# MCU.net
KiCad netlist of a schematic drawn in Altium Designer
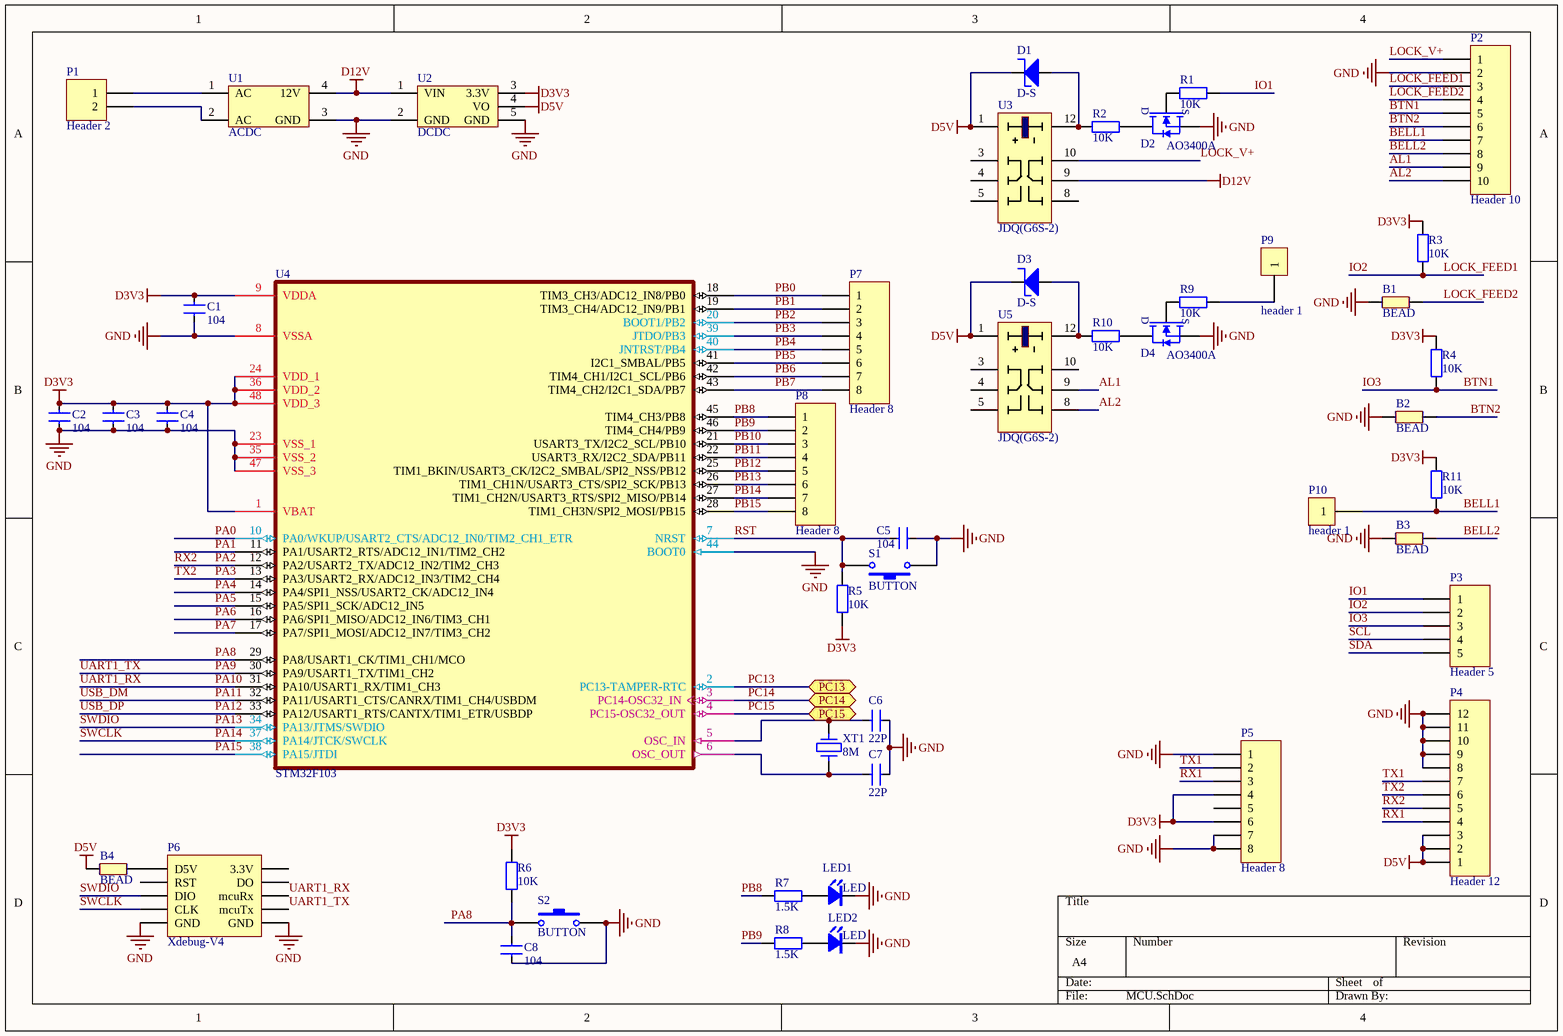
[diagram p0: MCU.SchDoc]

(export (version "E")
  (design (tool "Eeschema 10.0.6"))
  (components
    (comp (ref "B1")
      (value "BEAD")
      (footprint "0603L")
      (description "磁珠")
      (libsource (lib "lib_AD") (part "BEAD"))
    )
    (comp (ref "B2")
      (value "BEAD")
      (footprint "0603L")
      (description "磁珠")
      (libsource (lib "lib_AD") (part "BEAD"))
    )
    (comp (ref "B3")
      (value "BEAD")
      (footprint "0603L")
      (description "磁珠")
      (libsource (lib "lib_AD") (part "BEAD"))
    )
    (comp (ref "B4")
      (value "BEAD")
      (footprint "0603L")
      (description "磁珠")
      (libsource (lib "lib_AD") (part "BEAD"))
    )
    (comp (ref "C1")
      (value "104")
      (footprint "0603C")
      (description "普通小电容")
      (libsource (lib "lib_GMDZ") (part "CAP"))
    )
    (comp (ref "C2")
      (value "104")
      (footprint "0603C")
      (description "普通小电容")
      (libsource (lib "lib_GMDZ") (part "CAP"))
    )
    (comp (ref "C3")
      (value "104")
      (footprint "0603C")
      (description "普通小电容")
      (libsource (lib "lib_GMDZ") (part "CAP"))
    )
    (comp (ref "C4")
      (value "104")
      (footprint "0603C")
      (description "普通小电容")
      (libsource (lib "lib_GMDZ") (part "CAP"))
    )
    (comp (ref "C5")
      (value "104")
      (footprint "0603C")
      (description "普通小电容")
      (libsource (lib "lib_AD") (part "CAP"))
    )
    (comp (ref "C6")
      (value "22P")
      (footprint "0603C")
      (description "普通小电容")
      (libsource (lib "lib_AD") (part "CAP"))
    )
    (comp (ref "C7")
      (value "22P")
      (footprint "0603C")
      (description "普通小电容")
      (libsource (lib "lib_AD") (part "CAP"))
    )
    (comp (ref "C8")
      (value "104")
      (footprint "0603C")
      (description "普通小电容")
      (libsource (lib "lib_AD") (part "CAP"))
    )
    (comp (ref "D1")
      (value "D-S")
      (footprint "DO-214AC(SMA)")
      (description "肖特基二极管")
      (libsource (lib "lib_AD") (part "D-S"))
    )
    (comp (ref "D2")
      (value "AO3400A")
      (footprint "SOT23A")
      (description "NMOS")
      (libsource (lib "lib_AD") (part "MOS-N"))
    )
    (comp (ref "D3")
      (value "D-S")
      (footprint "DO-214AC(SMA)")
      (description "肖特基二极管")
      (libsource (lib "lib_AD") (part "D-S"))
    )
    (comp (ref "D4")
      (value "AO3400A")
      (footprint "SOT23A")
      (description "NMOS")
      (libsource (lib "lib_AD") (part "MOS-N"))
    )
    (comp (ref "LED1") (value "LED") (footprint "0805D") (libsource (lib "lib_AD") (part "LED")))
    (comp (ref "LED2") (value "LED") (footprint "0805D") (libsource (lib "lib_AD") (part "LED")))
    (comp (ref "P1")
      (value "Header 2")
      (footprint "KF128-5.08-2")
      (description "Header, 2-Pin")
      (fields (field (name "PUBLISHER") "Altium Limited"))
      (libsource (lib "Header") (part "Header 2"))
    )
    (comp (ref "P2")
      (value "Header 10")
      (footprint "KF128-5.08-10")
      (description "Header, 10-Pin")
      (fields (field (name "PUBLISHER") "Altium Limited"))
      (libsource (lib "lib_AD") (part "Header 10"))
    )
    (comp (ref "P3")
      (value "Header 5")
      (footprint "HDR1X5")
      (description "Header, 5-Pin")
      (fields (field (name "PUBLISHER") "Altium Limited"))
      (libsource (lib "lib_AD") (part "Header 5"))
    )
    (comp (ref "P4")
      (value "Header 12")
      (footprint "FFC/SM1.0-2H10")
      (description "Header, 12-Pin")
      (fields (field (name "PUBLISHER") "Altium Limited"))
      (libsource (lib "lib_AD") (part "Header 12"))
    )
    (comp (ref "P5")
      (value "Header 8")
      (footprint "1.25T-6P")
      (description "Header, 8-Pin")
      (fields (field (name "PUBLISHER") "Altium Limited"))
      (libsource (lib "lib_AD") (part "Header 8"))
    )
    (comp (ref "P6")
      (value "Xdebug-V4")
      (footprint "DC2.54-10")
      (description "单片机端")
      (libsource (lib "lib_AD") (part "Xdebug-V4"))
    )
    (comp (ref "P7")
      (value "Header 8")
      (footprint "HDR1X8")
      (description "Header, 8-Pin")
      (fields (field (name "PUBLISHER") "Altium Limited"))
      (libsource (lib "lib_AD") (part "Header 8"))
    )
    (comp (ref "P8")
      (value "Header 8")
      (footprint "HDR1X8")
      (description "Header, 8-Pin")
      (fields (field (name "PUBLISHER") "Altium Limited"))
      (libsource (lib "lib_AD") (part "Header 8"))
    )
    (comp (ref "P9") (value "header 1") (footprint "HDR1") (libsource (lib "") (part "header 1_1")))
    (comp (ref "P10") (value "header 1") (footprint "HDR1") (libsource (lib "lib_AD") (part "header 1")))
    (comp (ref "R1")
      (value "10K")
      (footprint "0603R")
      (description "普通电阻")
      (libsource (lib "lib_AD") (part "RES"))
    )
    (comp (ref "R2")
      (value "10K")
      (footprint "0603R")
      (description "普通电阻")
      (libsource (lib "lib_AD") (part "RES"))
    )
    (comp (ref "R3")
      (value "10K")
      (footprint "0603R")
      (description "普通电阻")
      (libsource (lib "") (part "RES_2"))
    )
    (comp (ref "R4")
      (value "10K")
      (footprint "0603R")
      (description "普通电阻")
      (libsource (lib "") (part "RES_2"))
    )
    (comp (ref "R5")
      (value "10K")
      (footprint "0603R")
      (description "普通电阻")
      (libsource (lib "") (part "RES_2"))
    )
    (comp (ref "R6")
      (value "10K")
      (footprint "0603R")
      (description "普通电阻")
      (libsource (lib "") (part "RES_3"))
    )
    (comp (ref "R7")
      (value "1.5K")
      (footprint "0603R")
      (description "普通电阻")
      (libsource (lib "") (part "RES_1"))
    )
    (comp (ref "R8")
      (value "1.5K")
      (footprint "0603R")
      (description "普通电阻")
      (libsource (lib "") (part "RES_1"))
    )
    (comp (ref "R9")
      (value "10K")
      (footprint "0603R")
      (description "普通电阻")
      (libsource (lib "lib_AD") (part "RES"))
    )
    (comp (ref "R10")
      (value "10K")
      (footprint "0603R")
      (description "普通电阻")
      (libsource (lib "lib_AD") (part "RES"))
    )
    (comp (ref "R11")
      (value "10K")
      (footprint "0603R")
      (description "普通电阻")
      (libsource (lib "") (part "RES_2"))
    )
    (comp (ref "S1") (value "BUTTON") (footprint "SW-3X4X2") (libsource (lib "lib_AD") (part "BUTTON")))
    (comp (ref "S2") (value "BUTTON") (footprint "SW-3X4X2") (libsource (lib "lib_AD") (part "BUTTON")))
    (comp (ref "U1") (value "ACDC") (footprint "ACDC") (libsource (lib "Misc") (part "ACDC12")))
    (comp (ref "U2") (value "DCDC") (footprint "DCDC") (libsource (lib "lib_AD") (part "DCDC")))
    (comp (ref "U3")
      (value "JDQ(G6S-2)")
      (footprint "JDQ-G6S-2")
      (description "继电器（G6S-2 5VDC）")
      (libsource (lib "lib_AD") (part "JDQ(G6S-2)"))
    )
    (comp (ref "U4") (value "STM32F103") (footprint "LQFP48") (libsource (lib "lib_GMDZ") (part "STM32F103")))
    (comp (ref "U5")
      (value "JDQ(G6S-2)")
      (footprint "JDQ-G6S-2")
      (description "继电器（G6S-2 5VDC）")
      (libsource (lib "lib_AD") (part "JDQ(G6S-2)"))
    )
    (comp (ref "XT1")
      (value "8M")
      (footprint "5032")
      (description "晶振")
      (libsource (lib "lib_GMDZ") (part "XT"))
    )
  )
  (nets
    (net (code "1") (name "/AL1") (class "Default")
      (node (ref "P2") (pin "9") (pinfunction "9_9") (pintype "passive"))
      (node (ref "U5") (pin "9") (pinfunction "9_9") (pintype "passive"))
    )
    (net (code "2") (name "/AL2") (class "Default")
      (node (ref "P2") (pin "10") (pinfunction "10_10") (pintype "passive"))
      (node (ref "U5") (pin "8") (pinfunction "8_8") (pintype "passive"))
    )
    (net (code "3") (name "/BELL1") (class "Default")
      (node (ref "P10") (pin "1") (pinfunction "1_1") (pintype "passive"))
      (node (ref "P2") (pin "7") (pinfunction "7_7") (pintype "passive"))
      (node (ref "R11") (pin "1") (pinfunction "1_1") (pintype "passive"))
    )
    (net (code "4") (name "/BELL2") (class "Default")
      (node (ref "B3") (pin "1") (pinfunction "1_1") (pintype "passive"))
      (node (ref "P2") (pin "8") (pinfunction "8_8") (pintype "passive"))
    )
    (net (code "5") (name "/BTN1") (class "Default")
      (node (ref "P2") (pin "5") (pinfunction "5_5") (pintype "passive"))
      (node (ref "P3") (pin "3") (pinfunction "3_3") (pintype "passive"))
      (node (ref "R4") (pin "1") (pinfunction "1_1") (pintype "passive"))
    )
    (net (code "6") (name "/BTN2") (class "Default")
      (node (ref "B2") (pin "1") (pinfunction "1_1") (pintype "passive"))
      (node (ref "P2") (pin "6") (pinfunction "6_6") (pintype "passive"))
    )
    (net (code "10") (name "/IO1") (class "Default")
      (node (ref "P3") (pin "1") (pinfunction "1_1") (pintype "passive"))
      (node (ref "R1") (pin "2") (pinfunction "2_2") (pintype "passive"))
    )
    (net (code "11") (name "/IO2") (class "Default")
      (node (ref "P2") (pin "3") (pinfunction "3_3") (pintype "passive"))
      (node (ref "P3") (pin "2") (pinfunction "2_2") (pintype "passive"))
      (node (ref "R3") (pin "1") (pinfunction "1_1") (pintype "passive"))
    )
    (net (code "12") (name "/LOCK_FEED2") (class "Default")
      (node (ref "B1") (pin "1") (pinfunction "1_1") (pintype "passive"))
      (node (ref "P2") (pin "4") (pinfunction "4_4") (pintype "passive"))
    )
    (net (code "13") (name "/LOCK_V+") (class "Default")
      (node (ref "P2") (pin "1") (pinfunction "1_1") (pintype "passive"))
      (node (ref "U3") (pin "10") (pinfunction "10_10") (pintype "passive"))
    )
    (net (code "14") (name "/PA0") (class "Default")
      (node (ref "U4") (pin "10") (pinfunction "PA0/WKUP/USART2_CTS/ADC12_IN0/TIM2_CH1_ETR_10") (pintype "bidirectional"))
    )
    (net (code "15") (name "/PA1") (class "Default")
      (node (ref "U4") (pin "11") (pinfunction "PA1/USART2_RTS/ADC12_IN1/TIM2_CH2_11") (pintype "bidirectional"))
    )
    (net (code "16") (name "/PA2") (class "Default")
      (node (ref "P4") (pin "5") (pinfunction "5_5") (pintype "passive"))
      (node (ref "U4") (pin "12") (pinfunction "PA2/USART2_TX/ADC12_IN2/TIM2_CH3_12") (pintype "bidirectional"))
    )
    (net (code "17") (name "/PA3") (class "Default")
      (node (ref "P4") (pin "6") (pinfunction "6_6") (pintype "passive"))
      (node (ref "U4") (pin "13") (pinfunction "PA3/USART2_RX/ADC12_IN3/TIM2_CH4_13") (pintype "bidirectional"))
    )
    (net (code "18") (name "/PA4") (class "Default")
      (node (ref "U4") (pin "14") (pinfunction "PA4/SPI1_NSS/USART2_CK/ADC12_IN4_14") (pintype "bidirectional"))
    )
    (net (code "19") (name "/PA5") (class "Default")
      (node (ref "U4") (pin "15") (pinfunction "PA5/SPI1_SCK/ADC12_IN5_15") (pintype "bidirectional"))
    )
    (net (code "20") (name "/PA6") (class "Default")
      (node (ref "U4") (pin "16") (pinfunction "PA6/SPI1_MISO/ADC12_IN6/TIM3_CH1_16") (pintype "bidirectional"))
    )
    (net (code "21") (name "/PA7") (class "Default")
      (node (ref "U4") (pin "17") (pinfunction "PA7/SPI1_MOSI/ADC12_IN7/TIM3_CH2_17") (pintype "bidirectional"))
    )
    (net (code "22") (name "/PA8") (class "Default")
      (node (ref "C8") (pin "2") (pinfunction "2_2") (pintype "passive"))
      (node (ref "R6") (pin "2") (pinfunction "2_2") (pintype "passive"))
      (node (ref "S2") (pin "1") (pinfunction "1_1") (pintype "passive"))
      (node (ref "U4") (pin "29") (pinfunction "PA8/USART1_CK/TIM1_CH1/MCO_29") (pintype "bidirectional"))
    )
    (net (code "23") (name "/PA9") (class "Default")
      (node (ref "P6") (pin "8") (pinfunction "mcuTx_8") (pintype "passive"))
      (node (ref "U4") (pin "30") (pinfunction "PA9/USART1_TX/TIM1_CH2_30") (pintype "bidirectional"))
    )
    (net (code "24") (name "/PA10") (class "Default")
      (node (ref "P6") (pin "6") (pinfunction "mcuRx_6") (pintype "passive"))
      (node (ref "U4") (pin "31") (pinfunction "PA10/USART1_RX/TIM1_CH3_31") (pintype "bidirectional"))
    )
    (net (code "25") (name "/PA11") (class "Default")
      (node (ref "U4") (pin "32") (pinfunction "PA11/USART1_CTS/CANRX/TIM1_CH4/USBDM_32") (pintype "bidirectional"))
    )
    (net (code "26") (name "/PA12") (class "Default")
      (node (ref "U4") (pin "33") (pinfunction "PA12/USART1_RTS/CANTX/TIM1_ETR/USBDP_33") (pintype "bidirectional"))
    )
    (net (code "27") (name "/PA13") (class "Default")
      (node (ref "P6") (pin "5") (pinfunction "DIO_5") (pintype "passive"))
      (node (ref "U4") (pin "34") (pinfunction "PA13/JTMS/SWDIO_34") (pintype "bidirectional"))
    )
    (net (code "28") (name "/PA14") (class "Default")
      (node (ref "P6") (pin "7") (pinfunction "CLK_7") (pintype "passive"))
      (node (ref "U4") (pin "37") (pinfunction "PA14/JTCK/SWCLK_37") (pintype "bidirectional"))
    )
    (net (code "29") (name "/PA15") (class "Default")
      (node (ref "U4") (pin "38") (pinfunction "PA15/JTDI_38") (pintype "bidirectional"))
    )
    (net (code "30") (name "/PB0") (class "Default")
      (node (ref "P7") (pin "1") (pinfunction "1_1") (pintype "passive"))
      (node (ref "U4") (pin "18") (pinfunction "TIM3_CH3/ADC12_IN8/PB0_18") (pintype "bidirectional"))
    )
    (net (code "31") (name "/PB1") (class "Default")
      (node (ref "P7") (pin "2") (pinfunction "2_2") (pintype "passive"))
      (node (ref "U4") (pin "19") (pinfunction "TIM3_CH4/ADC12_IN9/PB1_19") (pintype "bidirectional"))
    )
    (net (code "32") (name "/PB2") (class "Default")
      (node (ref "P7") (pin "3") (pinfunction "3_3") (pintype "passive"))
      (node (ref "U4") (pin "20") (pinfunction "BOOT1/PB2_20") (pintype "bidirectional"))
    )
    (net (code "33") (name "/PB3") (class "Default")
      (node (ref "P7") (pin "4") (pinfunction "4_4") (pintype "passive"))
      (node (ref "U4") (pin "39") (pinfunction "JTDO/PB3_39") (pintype "bidirectional"))
    )
    (net (code "34") (name "/PB4") (class "Default")
      (node (ref "P7") (pin "5") (pinfunction "5_5") (pintype "passive"))
      (node (ref "U4") (pin "40") (pinfunction "JNTRST/PB4_40") (pintype "bidirectional"))
    )
    (net (code "35") (name "/PB5") (class "Default")
      (node (ref "P7") (pin "6") (pinfunction "6_6") (pintype "passive"))
      (node (ref "U4") (pin "41") (pinfunction "I2C1_SMBAL/PB5_41") (pintype "bidirectional"))
    )
    (net (code "36") (name "/PB6") (class "Default")
      (node (ref "P7") (pin "7") (pinfunction "7_7") (pintype "passive"))
      (node (ref "U4") (pin "42") (pinfunction "TIM4_CH1/I2C1_SCL/PB6_42") (pintype "bidirectional"))
    )
    (net (code "37") (name "/PB7") (class "Default")
      (node (ref "P7") (pin "8") (pinfunction "8_8") (pintype "passive"))
      (node (ref "U4") (pin "43") (pinfunction "TIM4_CH2/I2C1_SDA/PB7_43") (pintype "bidirectional"))
    )
    (net (code "38") (name "/PB8") (class "Default")
      (node (ref "P8") (pin "1") (pinfunction "1_1") (pintype "passive"))
      (node (ref "R7") (pin "1") (pinfunction "1_1") (pintype "passive"))
      (node (ref "U4") (pin "45") (pinfunction "TIM4_CH3/PB8_45") (pintype "bidirectional"))
    )
    (net (code "39") (name "/PB9") (class "Default")
      (node (ref "P8") (pin "2") (pinfunction "2_2") (pintype "passive"))
      (node (ref "R8") (pin "1") (pinfunction "1_1") (pintype "passive"))
      (node (ref "U4") (pin "46") (pinfunction "TIM4_CH4/PB9_46") (pintype "bidirectional"))
    )
    (net (code "40") (name "/PB10") (class "Default")
      (node (ref "P8") (pin "3") (pinfunction "3_3") (pintype "passive"))
      (node (ref "U4") (pin "21") (pinfunction "USART3_TX/I2C2_SCL/PB10_21") (pintype "bidirectional"))
    )
    (net (code "41") (name "/PB11") (class "Default")
      (node (ref "P8") (pin "4") (pinfunction "4_4") (pintype "passive"))
      (node (ref "U4") (pin "22") (pinfunction "USART3_RX/I2C2_SDA/PB11_22") (pintype "bidirectional"))
    )
    (net (code "42") (name "/PB12") (class "Default")
      (node (ref "P8") (pin "5") (pinfunction "5_5") (pintype "passive"))
      (node (ref "U4") (pin "25") (pinfunction "TIM1_BKIN/USART3_CK/I2C2_SMBAL/SPI2_NSS/PB12_25") (pintype "bidirectional"))
    )
    (net (code "43") (name "/PB13") (class "Default")
      (node (ref "P8") (pin "6") (pinfunction "6_6") (pintype "passive"))
      (node (ref "U4") (pin "26") (pinfunction "TIM1_CH1N/USART3_CTS/SPI2_SCK/PB13_26") (pintype "bidirectional"))
    )
    (net (code "44") (name "/PB14") (class "Default")
      (node (ref "P8") (pin "7") (pinfunction "7_7") (pintype "passive"))
      (node (ref "U4") (pin "27") (pinfunction "TIM1_CH2N/USART3_RTS/SPI2_MISO/PB14_27") (pintype "bidirectional"))
    )
    (net (code "45") (name "/PB15") (class "Default")
      (node (ref "P8") (pin "8") (pinfunction "8_8") (pintype "passive"))
      (node (ref "U4") (pin "28") (pinfunction "TIM1_CH3N/SPI2_MOSI/PB15_28") (pintype "bidirectional"))
    )
    (net (code "46") (name "/PC13") (class "Default")
      (node (ref "U4") (pin "2") (pinfunction "PC13-TAMPER-RTC_2") (pintype "bidirectional"))
    )
    (net (code "47") (name "/PC14") (class "Default")
      (node (ref "U4") (pin "3") (pinfunction "PC14-OSC32_IN_3") (pintype "bidirectional"))
    )
    (net (code "48") (name "/PC15") (class "Default")
      (node (ref "U4") (pin "4") (pinfunction "PC15-OSC32_OUT_4") (pintype "bidirectional"))
    )
    (net (code "49") (name "/RST") (class "Default")
      (node (ref "C5") (pin "1") (pinfunction "1_1") (pintype "passive"))
      (node (ref "R5") (pin "2") (pinfunction "2_2") (pintype "passive"))
      (node (ref "S1") (pin "2") (pinfunction "2_2") (pintype "passive"))
      (node (ref "U4") (pin "7") (pinfunction "NRST_7") (pintype "bidirectional"))
    )
    (net (code "50") (name "/RX1") (class "Default")
      (node (ref "P4") (pin "4") (pinfunction "4_4") (pintype "passive"))
      (node (ref "P5") (pin "3") (pinfunction "3_3") (pintype "passive"))
    )
    (net (code "51") (name "/SCL") (class "Default")
      (node (ref "P3") (pin "4") (pinfunction "4_4") (pintype "passive"))
    )
    (net (code "52") (name "/SDA") (class "Default")
      (node (ref "P3") (pin "5") (pinfunction "5_5") (pintype "passive"))
    )
    (net (code "53") (name "/TX1") (class "Default")
      (node (ref "P4") (pin "7") (pinfunction "7_7") (pintype "passive"))
      (node (ref "P5") (pin "2") (pinfunction "2_2") (pintype "passive"))
    )
    (net (code "54") (name "D3V3") (class "Default")
      (node (ref "C1") (pin "2") (pinfunction "2_2") (pintype "passive"))
      (node (ref "C2") (pin "2") (pinfunction "2_2") (pintype "passive"))
      (node (ref "C3") (pin "1") (pinfunction "1_1") (pintype "passive"))
      (node (ref "C4") (pin "2") (pinfunction "2_2") (pintype "passive"))
      (node (ref "P5") (pin "4") (pinfunction "4_4") (pintype "passive"))
      (node (ref "P5") (pin "6") (pinfunction "6_6") (pintype "passive"))
      (node (ref "R11") (pin "2") (pinfunction "2_2") (pintype "passive"))
      (node (ref "R3") (pin "2") (pinfunction "2_2") (pintype "passive"))
      (node (ref "R4") (pin "2") (pinfunction "2_2") (pintype "passive"))
      (node (ref "R5") (pin "1") (pinfunction "1_1") (pintype "passive"))
      (node (ref "R6") (pin "1") (pinfunction "1_1") (pintype "passive"))
      (node (ref "U2") (pin "3") (pinfunction "3.3V_3") (pintype "passive"))
      (node (ref "U4") (pin "1") (pinfunction "VBAT_1") (pintype "power_in"))
      (node (ref "U4") (pin "24") (pinfunction "VDD_1_24") (pintype "power_in"))
      (node (ref "U4") (pin "36") (pinfunction "VDD_2_36") (pintype "power_in"))
      (node (ref "U4") (pin "48") (pinfunction "VDD_3_48") (pintype "power_in"))
      (node (ref "U4") (pin "9") (pinfunction "VDDA_9") (pintype "power_in"))
    )
    (net (code "55") (name "D5V") (class "Default")
      (node (ref "B4") (pin "2") (pinfunction "2_2") (pintype "passive"))
      (node (ref "D1") (pin "K") (pinfunction "2_K") (pintype "passive"))
      (node (ref "D3") (pin "K") (pinfunction "2_K") (pintype "passive"))
      (node (ref "P4") (pin "1") (pinfunction "1_1") (pintype "passive"))
      (node (ref "P4") (pin "2") (pinfunction "2_2") (pintype "passive"))
      (node (ref "P4") (pin "3") (pinfunction "3_3") (pintype "passive"))
      (node (ref "U2") (pin "4") (pinfunction "VO_4") (pintype "passive"))
      (node (ref "U3") (pin "1") (pinfunction "1_1") (pintype "passive"))
      (node (ref "U5") (pin "1") (pinfunction "1_1") (pintype "passive"))
    )
    (net (code "56") (name "D12V") (class "Default")
      (node (ref "U1") (pin "4") (pinfunction "12V_4") (pintype "passive"))
      (node (ref "U2") (pin "1") (pinfunction "VIN_1") (pintype "passive"))
      (node (ref "U3") (pin "9") (pinfunction "9_9") (pintype "passive"))
    )
    (net (code "57") (name "GND") (class "Default")
      (node (ref "B1") (pin "2") (pinfunction "2_2") (pintype "passive"))
      (node (ref "B2") (pin "2") (pinfunction "2_2") (pintype "passive"))
      (node (ref "B3") (pin "2") (pinfunction "2_2") (pintype "passive"))
      (node (ref "C1") (pin "1") (pinfunction "1_1") (pintype "passive"))
      (node (ref "C2") (pin "1") (pinfunction "1_1") (pintype "passive"))
      (node (ref "C3") (pin "2") (pinfunction "2_2") (pintype "passive"))
      (node (ref "C4") (pin "1") (pinfunction "1_1") (pintype "passive"))
      (node (ref "C5") (pin "2") (pinfunction "2_2") (pintype "passive"))
      (node (ref "C6") (pin "2") (pinfunction "2_2") (pintype "passive"))
      (node (ref "C7") (pin "2") (pinfunction "2_2") (pintype "passive"))
      (node (ref "C8") (pin "1") (pinfunction "1_1") (pintype "passive"))
      (node (ref "D2") (pin "2") (pinfunction "S_2") (pintype "passive"))
      (node (ref "D4") (pin "2") (pinfunction "S_2") (pintype "passive"))
      (node (ref "LED1") (pin "K") (pinfunction "2_K") (pintype "passive"))
      (node (ref "LED2") (pin "K") (pinfunction "2_K") (pintype "passive"))
      (node (ref "P2") (pin "2") (pinfunction "2_2") (pintype "passive"))
      (node (ref "P4") (pin "10") (pinfunction "10_10") (pintype "passive"))
      (node (ref "P4") (pin "11") (pinfunction "11_11") (pintype "passive"))
      (node (ref "P4") (pin "12") (pinfunction "12_12") (pintype "passive"))
      (node (ref "P4") (pin "8") (pinfunction "8_8") (pintype "passive"))
      (node (ref "P4") (pin "9") (pinfunction "9_9") (pintype "passive"))
      (node (ref "P5") (pin "1") (pinfunction "1_1") (pintype "passive"))
      (node (ref "P5") (pin "7") (pinfunction "7_7") (pintype "passive"))
      (node (ref "P5") (pin "8") (pinfunction "8_8") (pintype "passive"))
      (node (ref "P6") (pin "10") (pinfunction "GND_10") (pintype "passive"))
      (node (ref "P6") (pin "9") (pinfunction "GND_9") (pintype "passive"))
      (node (ref "S1") (pin "1") (pinfunction "1_1") (pintype "passive"))
      (node (ref "S2") (pin "2") (pinfunction "2_2") (pintype "passive"))
      (node (ref "U1") (pin "3") (pinfunction "GND_3") (pintype "passive"))
      (node (ref "U2") (pin "2") (pinfunction "GND_2") (pintype "passive"))
      (node (ref "U2") (pin "5") (pinfunction "GND_5") (pintype "passive"))
      (node (ref "U4") (pin "23") (pinfunction "VSS_1_23") (pintype "power_in"))
      (node (ref "U4") (pin "35") (pinfunction "VSS_2_35") (pintype "power_in"))
      (node (ref "U4") (pin "44") (pinfunction "BOOT0_44") (pintype "input"))
      (node (ref "U4") (pin "47") (pinfunction "VSS_3_47") (pintype "power_in"))
      (node (ref "U4") (pin "8") (pinfunction "VSSA_8") (pintype "power_in"))
    )
    (net (code "58") (name "Net-(D1-1)") (class "Default")
      (node (ref "D1") (pin "A") (pinfunction "1_A") (pintype "passive"))
      (node (ref "R2") (pin "1") (pinfunction "1_1") (pintype "passive"))
      (node (ref "U3") (pin "12") (pinfunction "12_12") (pintype "passive"))
    )
    (net (code "59") (name "Net-(D2-D)") (class "Default")
      (node (ref "D2") (pin "3") (pinfunction "D_3") (pintype "passive"))
      (node (ref "R2") (pin "2") (pinfunction "2_2") (pintype "passive"))
    )
    (net (code "60") (name "Net-(D2-G)") (class "Default")
      (node (ref "D2") (pin "1") (pinfunction "G_1") (pintype "passive"))
      (node (ref "R1") (pin "1") (pinfunction "1_1") (pintype "passive"))
    )
    (net (code "61") (name "Net-(D3-1)") (class "Default")
      (node (ref "D3") (pin "A") (pinfunction "1_A") (pintype "passive"))
      (node (ref "R10") (pin "1") (pinfunction "1_1") (pintype "passive"))
      (node (ref "U5") (pin "12") (pinfunction "12_12") (pintype "passive"))
    )
    (net (code "62") (name "Net-(D4-D)") (class "Default")
      (node (ref "D4") (pin "3") (pinfunction "D_3") (pintype "passive"))
      (node (ref "R10") (pin "2") (pinfunction "2_2") (pintype "passive"))
    )
    (net (code "63") (name "Net-(D4-G)") (class "Default")
      (node (ref "D4") (pin "1") (pinfunction "G_1") (pintype "passive"))
      (node (ref "R9") (pin "1") (pinfunction "1_1") (pintype "passive"))
    )
    (net (code "64") (name "Net-(LED1-1)") (class "Default")
      (node (ref "LED1") (pin "A") (pinfunction "1_A") (pintype "passive"))
      (node (ref "R7") (pin "2") (pinfunction "2_2") (pintype "passive"))
    )
    (net (code "65") (name "Net-(LED2-1)") (class "Default")
      (node (ref "LED2") (pin "A") (pinfunction "1_A") (pintype "passive"))
      (node (ref "R8") (pin "2") (pinfunction "2_2") (pintype "passive"))
    )
    (net (code "66") (name "Net-(P1-Pad1)") (class "Default")
      (node (ref "P1") (pin "1") (pinfunction "1_1") (pintype "passive"))
      (node (ref "U1") (pin "1") (pinfunction "AC_1") (pintype "passive"))
    )
    (net (code "67") (name "Net-(P1-Pad2)") (class "Default")
      (node (ref "P1") (pin "2") (pinfunction "2_2") (pintype "passive"))
      (node (ref "U1") (pin "2") (pinfunction "AC_2") (pintype "passive"))
    )
    (net (code "68") (name "Net-(P6-D5V)") (class "Default")
      (node (ref "B4") (pin "1") (pinfunction "1_1") (pintype "passive"))
      (node (ref "P6") (pin "1") (pinfunction "D5V_1") (pintype "passive"))
    )
    (net (code "69") (name "Net-(P9-Pad1)") (class "Default")
      (node (ref "P9") (pin "1") (pinfunction "1_1") (pintype "passive"))
      (node (ref "R9") (pin "2") (pinfunction "2_2") (pintype "passive"))
    )
    (net (code "70") (name "Net-(U4-OSC_IN)") (class "Default")
      (node (ref "C6") (pin "1") (pinfunction "1_1") (pintype "passive"))
      (node (ref "U4") (pin "5") (pinfunction "OSC_IN_5") (pintype "input"))
      (node (ref "XT1") (pin "1") (pinfunction "1_1") (pintype "passive"))
    )
    (net (code "71") (name "Net-(U4-OSC_OUT)") (class "Default")
      (node (ref "C7") (pin "1") (pinfunction "1_1") (pintype "passive"))
      (node (ref "U4") (pin "6") (pinfunction "OSC_OUT_6") (pintype "output"))
      (node (ref "XT1") (pin "2") (pinfunction "2_2") (pintype "passive"))
    )
    (net (code "72") (name "unconnected-(P5-Pad5)") (class "Default")
      (node (ref "P5") (pin "5") (pinfunction "5_5") (pintype "passive"))
    )
    (net (code "73") (name "unconnected-(P6-3.3V-Pad2)") (class "Default")
      (node (ref "P6") (pin "2") (pinfunction "3.3V_2") (pintype "passive"))
    )
    (net (code "74") (name "unconnected-(P6-DO-Pad4)") (class "Default")
      (node (ref "P6") (pin "4") (pinfunction "DO_4") (pintype "passive"))
    )
    (net (code "75") (name "unconnected-(P6-RST-Pad3)") (class "Default")
      (node (ref "P6") (pin "3") (pinfunction "RST_3") (pintype "passive"))
    )
    (net (code "76") (name "unconnected-(U3-Pad3)") (class "Default")
      (node (ref "U3") (pin "3") (pinfunction "3_3") (pintype "passive"))
    )
    (net (code "77") (name "unconnected-(U3-Pad4)") (class "Default")
      (node (ref "U3") (pin "4") (pinfunction "4_4") (pintype "passive"))
    )
    (net (code "78") (name "unconnected-(U3-Pad5)") (class "Default")
      (node (ref "U3") (pin "5") (pinfunction "5_5") (pintype "passive"))
    )
    (net (code "79") (name "unconnected-(U3-Pad8)") (class "Default")
      (node (ref "U3") (pin "8") (pinfunction "8_8") (pintype "passive"))
    )
    (net (code "80") (name "unconnected-(U5-Pad3)") (class "Default")
      (node (ref "U5") (pin "3") (pinfunction "3_3") (pintype "passive"))
    )
    (net (code "81") (name "unconnected-(U5-Pad4)") (class "Default")
      (node (ref "U5") (pin "4") (pinfunction "4_4") (pintype "passive"))
    )
    (net (code "82") (name "unconnected-(U5-Pad5)") (class "Default")
      (node (ref "U5") (pin "5") (pinfunction "5_5") (pintype "passive"))
    )
    (net (code "83") (name "unconnected-(U5-Pad10)") (class "Default")
      (node (ref "U5") (pin "10") (pinfunction "10_10") (pintype "passive"))
    )
  )
)
